# L6201PS_Small.net
KiCad netlist of a schematic drawn in EAGLE
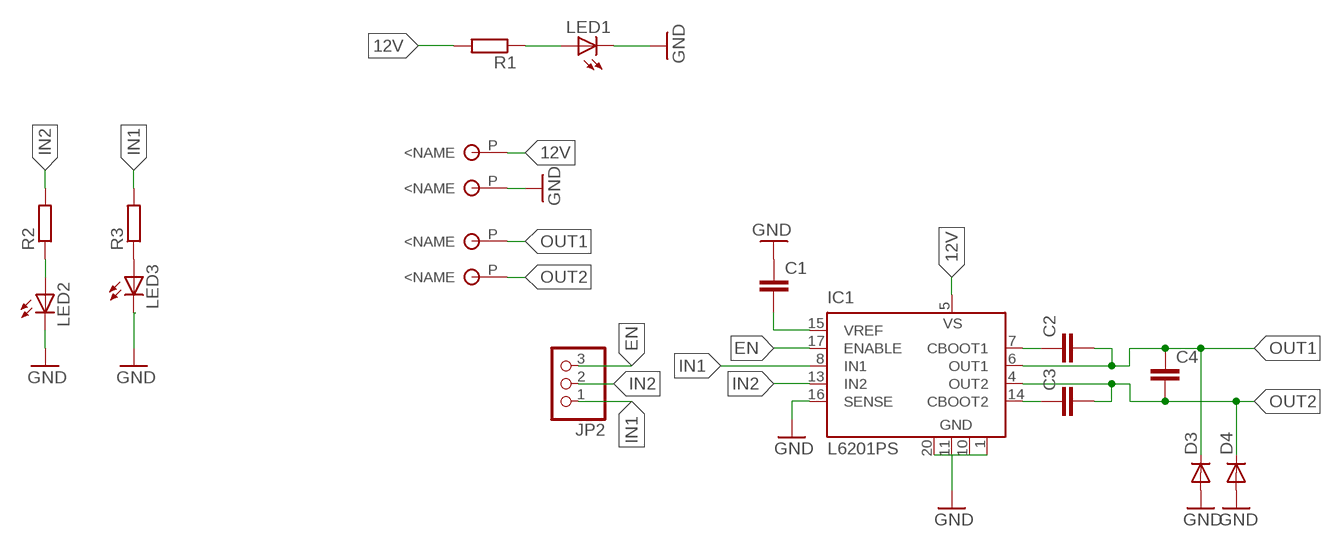
[diagram p0: schematic, sheet 1]

(export (version "E")
  (design (tool "Eeschema 10.0.6"))
  (components
    (comp (ref "C1")
      (value "C-EUC0603")
      (footprint "eagle-import:C0603")
      (libsource (lib "eagle-import") (part "C-EUC0603"))
    )
    (comp (ref "C2")
      (value "C-EUC0603")
      (footprint "eagle-import:C0603")
      (libsource (lib "eagle-import") (part "C-EUC0603"))
    )
    (comp (ref "C3")
      (value "C-EUC0603")
      (footprint "eagle-import:C0603")
      (libsource (lib "eagle-import") (part "C-EUC0603"))
    )
    (comp (ref "C4")
      (value "C-EUC0603")
      (footprint "eagle-import:C0603")
      (libsource (lib "eagle-import") (part "C-EUC0603"))
    )
    (comp (ref "D3")
      (value "DIODE-DO214AC")
      (footprint "eagle-import:DO214AC")
      (libsource (lib "eagle-import") (part "DIODE-DO214AC"))
    )
    (comp (ref "D4")
      (value "DIODE-DO214AC")
      (footprint "eagle-import:DO214AC")
      (libsource (lib "eagle-import") (part "DIODE-DO214AC"))
    )
    (comp (ref "IC1")
      (value "L6201PS")
      (footprint "eagle-import:POWERSO-20")
      (fields (field (name "MF") "Arrow Electronics"))
      (libsource (lib "eagle-import") (part "L6201PS"))
    )
    (comp (ref "JP2")
      (value "PINHD-1X3")
      (footprint "eagle-import:1X03")
      (libsource (lib "eagle-import") (part "PINHD-1X3"))
    )
    (comp (ref "LED1")
      (value "LEDSML0603")
      (footprint "eagle-import:SML0603")
      (libsource (lib "eagle-import") (part "LEDSML0603"))
    )
    (comp (ref "LED2")
      (value "LEDSML0603")
      (footprint "eagle-import:SML0603")
      (libsource (lib "eagle-import") (part "LEDSML0603"))
    )
    (comp (ref "LED3")
      (value "LEDSML0603")
      (footprint "eagle-import:SML0603")
      (libsource (lib "eagle-import") (part "LEDSML0603"))
    )
    (comp (ref "R1")
      (value "R-EU_R0603")
      (footprint "eagle-import:R0603")
      (libsource (lib "eagle-import") (part "R-EU_R0603"))
    )
    (comp (ref "R2")
      (value "R-EU_R0603")
      (footprint "eagle-import:R0603")
      (libsource (lib "eagle-import") (part "R-EU_R0603"))
    )
    (comp (ref "R3")
      (value "R-EU_R0603")
      (footprint "eagle-import:R0603")
      (libsource (lib "eagle-import") (part "R-EU_R0603"))
    )
    (comp (ref "U$1")
      (value "CU-SPACER")
      (footprint "eagle-import:CU-SPACER")
      (libsource (lib "eagle-import") (part "CU-SPACER"))
    )
    (comp (ref "U$2")
      (value "CU-SPACER")
      (footprint "eagle-import:CU-SPACER")
      (libsource (lib "eagle-import") (part "CU-SPACER"))
    )
    (comp (ref "U$3")
      (value "CU-SPACER")
      (footprint "eagle-import:CU-SPACER")
      (libsource (lib "eagle-import") (part "CU-SPACER"))
    )
    (comp (ref "U$4")
      (value "CU-SPACER")
      (footprint "eagle-import:CU-SPACER")
      (libsource (lib "eagle-import") (part "CU-SPACER"))
    )
  )
  (nets
    (net (code "1") (name "12V") (class "Default")
      (node (ref "IC1") (pin "5") (pinfunction "VS_5") (pintype "power_in"))
      (node (ref "R1") (pin "2") (pinfunction "2_2") (pintype "passive"))
      (node (ref "U$2") (pin "P") (pinfunction "<NAME_P") (pintype "bidirectional"))
    )
    (net (code "2") (name "EN") (class "Default")
      (node (ref "IC1") (pin "17") (pinfunction "ENABLE_17") (pintype "input"))
      (node (ref "JP2") (pin "3") (pinfunction "3_3") (pintype "passive"))
    )
    (net (code "3") (name "GND") (class "Default")
      (node (ref "C1") (pin "1") (pinfunction "1_1") (pintype "passive"))
      (node (ref "D3") (pin "A") (pinfunction "A_A") (pintype "passive"))
      (node (ref "D4") (pin "A") (pinfunction "A_A") (pintype "passive"))
      (node (ref "IC1") (pin "1") (pinfunction "GND_1") (pintype "power_in"))
      (node (ref "IC1") (pin "10") (pinfunction "GND_10") (pintype "power_in"))
      (node (ref "IC1") (pin "11") (pinfunction "GND_11") (pintype "power_in"))
      (node (ref "IC1") (pin "16") (pinfunction "SENSE_16") (pintype "input"))
      (node (ref "IC1") (pin "20") (pinfunction "GND_20") (pintype "power_in"))
      (node (ref "LED1") (pin "C") (pinfunction "C_C") (pintype "passive"))
      (node (ref "LED2") (pin "C") (pinfunction "C_C") (pintype "passive"))
      (node (ref "LED3") (pin "C") (pinfunction "C_C") (pintype "passive"))
      (node (ref "U$1") (pin "P") (pinfunction "<NAME_P") (pintype "bidirectional"))
    )
    (net (code "4") (name "IN1") (class "Default")
      (node (ref "IC1") (pin "8") (pinfunction "IN1_8") (pintype "input"))
      (node (ref "JP2") (pin "1") (pinfunction "1_1") (pintype "passive"))
      (node (ref "R3") (pin "2") (pinfunction "2_2") (pintype "passive"))
    )
    (net (code "5") (name "IN2") (class "Default")
      (node (ref "IC1") (pin "13") (pinfunction "IN2_13") (pintype "input"))
      (node (ref "JP2") (pin "2") (pinfunction "2_2") (pintype "passive"))
      (node (ref "R2") (pin "2") (pinfunction "2_2") (pintype "passive"))
    )
    (net (code "6") (name "Net-(IC1-CBOOT1)") (class "Default")
      (node (ref "C2") (pin "1") (pinfunction "1_1") (pintype "passive"))
      (node (ref "IC1") (pin "7") (pinfunction "CBOOT1_7") (pintype "input"))
    )
    (net (code "7") (name "Net-(IC1-CBOOT2)") (class "Default")
      (node (ref "C3") (pin "1") (pinfunction "1_1") (pintype "passive"))
      (node (ref "IC1") (pin "14") (pinfunction "CBOOT2_14") (pintype "input"))
    )
    (net (code "8") (name "Net-(IC1-VREF)") (class "Default")
      (node (ref "C1") (pin "2") (pinfunction "2_2") (pintype "passive"))
      (node (ref "IC1") (pin "15") (pinfunction "VREF_15") (pintype "input"))
    )
    (net (code "9") (name "Net-(LED1-PadA)") (class "Default")
      (node (ref "LED1") (pin "A") (pinfunction "A_A") (pintype "passive"))
      (node (ref "R1") (pin "1") (pinfunction "1_1") (pintype "passive"))
    )
    (net (code "10") (name "Net-(LED2-PadA)") (class "Default")
      (node (ref "LED2") (pin "A") (pinfunction "A_A") (pintype "passive"))
      (node (ref "R2") (pin "1") (pinfunction "1_1") (pintype "passive"))
    )
    (net (code "11") (name "Net-(LED3-PadA)") (class "Default")
      (node (ref "LED3") (pin "A") (pinfunction "A_A") (pintype "passive"))
      (node (ref "R3") (pin "1") (pinfunction "1_1") (pintype "passive"))
    )
    (net (code "12") (name "OUT1") (class "Default")
      (node (ref "C2") (pin "2") (pinfunction "2_2") (pintype "passive"))
      (node (ref "C4") (pin "1") (pinfunction "1_1") (pintype "passive"))
      (node (ref "D3") (pin "C") (pinfunction "C_C") (pintype "passive"))
      (node (ref "IC1") (pin "6") (pinfunction "OUT1_6") (pintype "output"))
      (node (ref "U$3") (pin "P") (pinfunction "<NAME_P") (pintype "bidirectional"))
    )
    (net (code "13") (name "OUT2") (class "Default")
      (node (ref "C3") (pin "2") (pinfunction "2_2") (pintype "passive"))
      (node (ref "C4") (pin "2") (pinfunction "2_2") (pintype "passive"))
      (node (ref "D4") (pin "C") (pinfunction "C_C") (pintype "passive"))
      (node (ref "IC1") (pin "4") (pinfunction "OUT2_4") (pintype "output"))
      (node (ref "U$4") (pin "P") (pinfunction "<NAME_P") (pintype "bidirectional"))
    )
  )
)
